# VCOBoard.net
KiCad netlist of a schematic drawn in EAGLE
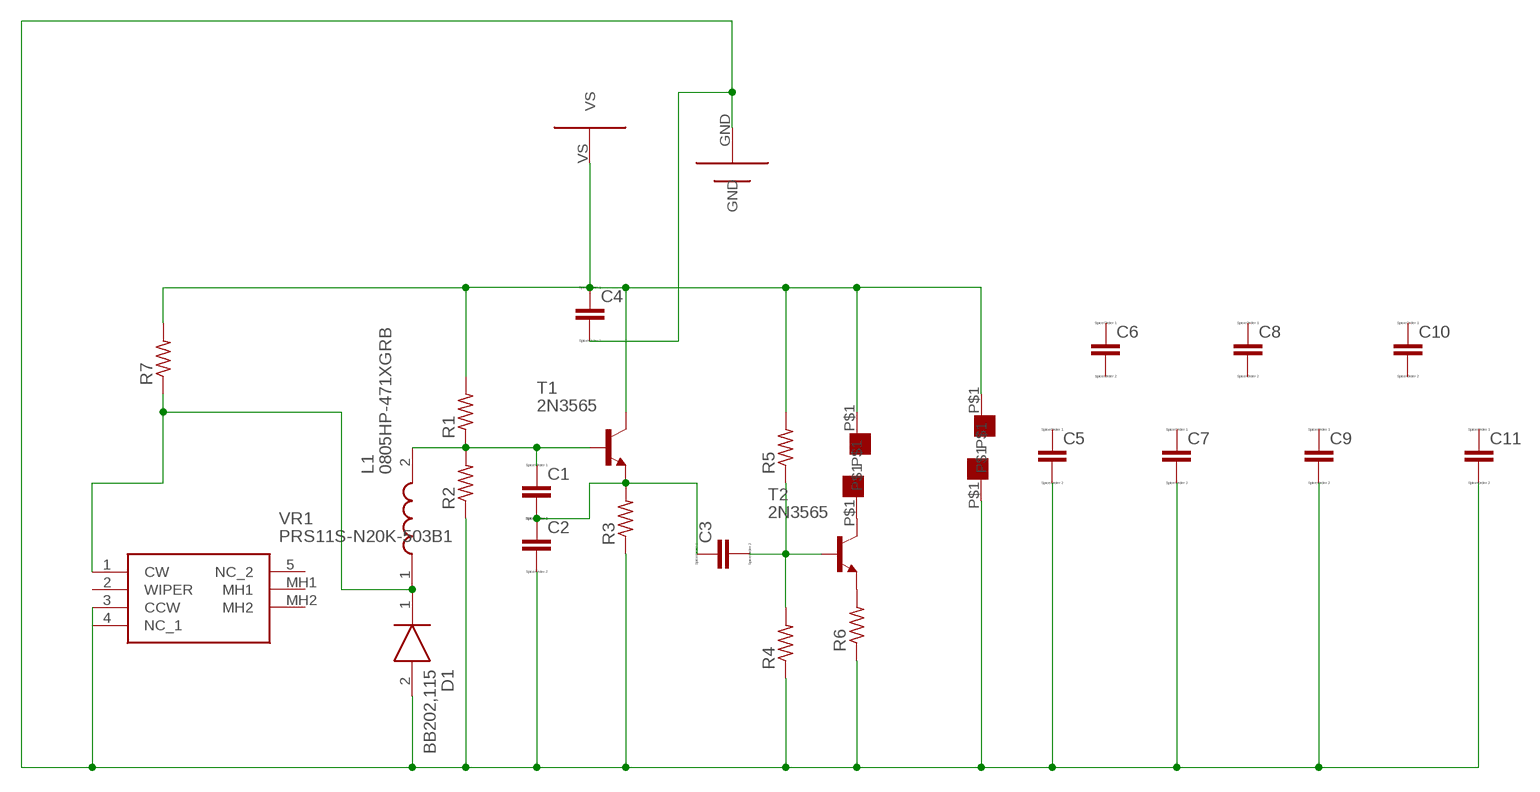
[diagram p0: schematic, sheet 1]

(export (version "E")
  (design (tool "Eeschema 10.0.6"))
  (components
    (comp (ref "C1") (value "C") (footprint "eagle-import:C0805") (libsource (lib "eagle-import") (part "C")))
    (comp (ref "C2") (value "C") (footprint "eagle-import:C0805") (libsource (lib "eagle-import") (part "C")))
    (comp (ref "C3") (value "C") (footprint "eagle-import:C0805") (libsource (lib "eagle-import") (part "C")))
    (comp (ref "C4") (value "C") (footprint "eagle-import:C0805") (libsource (lib "eagle-import") (part "C")))
    (comp (ref "C5") (value "C") (footprint "eagle-import:C0805") (libsource (lib "eagle-import") (part "C")))
    (comp (ref "C6") (value "C") (footprint "eagle-import:C0805") (libsource (lib "eagle-import") (part "C")))
    (comp (ref "C7") (value "C") (footprint "eagle-import:C0805") (libsource (lib "eagle-import") (part "C")))
    (comp (ref "C8") (value "C") (footprint "eagle-import:C0805") (libsource (lib "eagle-import") (part "C")))
    (comp (ref "C9") (value "C") (footprint "eagle-import:C0805") (libsource (lib "eagle-import") (part "C")))
    (comp (ref "C10")
      (value "C")
      (footprint "eagle-import:C0805")
      (libsource (lib "eagle-import") (part "C"))
    )
    (comp (ref "C11")
      (value "C")
      (footprint "eagle-import:C0805")
      (libsource (lib "eagle-import") (part "C"))
    )
    (comp (ref "D1")
      (value "BB202,115")
      (footprint "eagle-import:SODFL1608X65N")
      (fields (field (name "MOUSER_PART_NUMBER") "771-BB202-T/R"))
      (libsource (lib "eagle-import") (part "BB202,115"))
    )
    (comp (ref "L1")
      (value "0805HP-471XGRB")
      (footprint "eagle-import:INDPM2217X155N")
      (fields (field (name "MOUSER_PART_NUMBER") "994-0805HP-471XGRB"))
      (libsource (lib "eagle-import") (part "0805HP-471XGRB"))
    )
    (comp (ref "R1")
      (value "R-US_R0805")
      (footprint "eagle-import:R0805")
      (libsource (lib "eagle-import") (part "R-US_R0805"))
    )
    (comp (ref "R2")
      (value "R-US_R0805")
      (footprint "eagle-import:R0805")
      (libsource (lib "eagle-import") (part "R-US_R0805"))
    )
    (comp (ref "R3")
      (value "R-US_R0805")
      (footprint "eagle-import:R0805")
      (libsource (lib "eagle-import") (part "R-US_R0805"))
    )
    (comp (ref "R4")
      (value "R-US_R0805")
      (footprint "eagle-import:R0805")
      (libsource (lib "eagle-import") (part "R-US_R0805"))
    )
    (comp (ref "R5")
      (value "R-US_R0805")
      (footprint "eagle-import:R0805")
      (libsource (lib "eagle-import") (part "R-US_R0805"))
    )
    (comp (ref "R6")
      (value "R-US_R0805")
      (footprint "eagle-import:R0805")
      (libsource (lib "eagle-import") (part "R-US_R0805"))
    )
    (comp (ref "R7")
      (value "R-US_R0805")
      (footprint "eagle-import:R0805")
      (libsource (lib "eagle-import") (part "R-US_R0805"))
    )
    (comp (ref "T1")
      (value "2N3565")
      (footprint "eagle-import:TO92")
      (libsource (lib "eagle-import") (part "2N3565"))
    )
    (comp (ref "T2")
      (value "2N3565")
      (footprint "eagle-import:TO92")
      (libsource (lib "eagle-import") (part "2N3565"))
    )
    (comp (ref "U$1")
      (value "PAD")
      (footprint "eagle-import:PAD")
      (libsource (lib "eagle-import") (part "PAD"))
    )
    (comp (ref "U$2")
      (value "PAD")
      (footprint "eagle-import:PAD")
      (libsource (lib "eagle-import") (part "PAD"))
    )
    (comp (ref "U$3")
      (value "PAD")
      (footprint "eagle-import:PAD")
      (libsource (lib "eagle-import") (part "PAD"))
    )
    (comp (ref "U$4")
      (value "PAD")
      (footprint "eagle-import:PAD")
      (libsource (lib "eagle-import") (part "PAD"))
    )
    (comp (ref "U$5")
      (value "ALLIGATORCLIPS")
      (footprint "eagle-import:ALLIGATORCONNECTOR")
      (libsource (lib "eagle-import") (part "ALLIGATORCLIPS"))
    )
    (comp (ref "VR1")
      (value "PRS11S-N20K-503B1")
      (footprint "eagle-import:PRS11SN20K503B1")
      (fields (field (name "MOUSER_PART_NUMBER") "652-PRS11SN20K503B1"))
      (libsource (lib "eagle-import") (part "PRS11S-N20K-503B1"))
    )
  )
  (nets
    (net (code "1") (name "Net-(D1-A)") (class "Default")
      (node (ref "C11") (pin "2") (pinfunction "2_2") (pintype "passive"))
      (node (ref "C2") (pin "2") (pinfunction "2_2") (pintype "passive"))
      (node (ref "C4") (pin "2") (pinfunction "2_2") (pintype "passive"))
      (node (ref "C5") (pin "2") (pinfunction "2_2") (pintype "passive"))
      (node (ref "C7") (pin "2") (pinfunction "2_2") (pintype "passive"))
      (node (ref "C9") (pin "2") (pinfunction "2_2") (pintype "passive"))
      (node (ref "D1") (pin "2") (pinfunction "A_2") (pintype "bidirectional"))
      (node (ref "R2") (pin "1") (pinfunction "1_1") (pintype "passive"))
      (node (ref "R3") (pin "1") (pinfunction "1_1") (pintype "passive"))
      (node (ref "R4") (pin "1") (pinfunction "1_1") (pintype "passive"))
      (node (ref "R6") (pin "1") (pinfunction "1_1") (pintype "passive"))
      (node (ref "U$4") (pin "P$1") (pinfunction "P$1_P$1") (pintype "bidirectional"))
      (node (ref "U$5") (pin "GND") (pinfunction "GND_GND") (pintype "bidirectional"))
      (node (ref "VR1") (pin "3") (pinfunction "CCW_3") (pintype "bidirectional"))
    )
    (net (code "2") (name "Net-(D1-K)") (class "Default")
      (node (ref "D1") (pin "1") (pinfunction "K_1") (pintype "bidirectional"))
      (node (ref "L1") (pin "1") (pinfunction "1_1") (pintype "bidirectional"))
      (node (ref "R7") (pin "1") (pinfunction "1_1") (pintype "passive"))
      (node (ref "VR1") (pin "1") (pinfunction "CW_1") (pintype "bidirectional"))
    )
    (net (code "3") (name "Net-(T1-B)") (class "Default")
      (node (ref "C1") (pin "1") (pinfunction "1_1") (pintype "passive"))
      (node (ref "L1") (pin "2") (pinfunction "2_2") (pintype "bidirectional"))
      (node (ref "R1") (pin "1") (pinfunction "1_1") (pintype "passive"))
      (node (ref "R2") (pin "2") (pinfunction "2_2") (pintype "passive"))
      (node (ref "T1") (pin "2") (pinfunction "B_2") (pintype "passive"))
    )
    (net (code "4") (name "Net-(T1-C)") (class "Default")
      (node (ref "C4") (pin "1") (pinfunction "1_1") (pintype "passive"))
      (node (ref "R1") (pin "2") (pinfunction "2_2") (pintype "passive"))
      (node (ref "R5") (pin "2") (pinfunction "2_2") (pintype "passive"))
      (node (ref "R7") (pin "2") (pinfunction "2_2") (pintype "passive"))
      (node (ref "T1") (pin "1") (pinfunction "C_1") (pintype "passive"))
      (node (ref "U$2") (pin "P$1") (pinfunction "P$1_P$1") (pintype "bidirectional"))
      (node (ref "U$3") (pin "P$1") (pinfunction "P$1_P$1") (pintype "bidirectional"))
      (node (ref "U$5") (pin "VS") (pinfunction "VS_VS") (pintype "bidirectional"))
    )
    (net (code "5") (name "Net-(T1-E)") (class "Default")
      (node (ref "C1") (pin "2") (pinfunction "2_2") (pintype "passive"))
      (node (ref "C2") (pin "1") (pinfunction "1_1") (pintype "passive"))
      (node (ref "C3") (pin "1") (pinfunction "1_1") (pintype "passive"))
      (node (ref "R3") (pin "2") (pinfunction "2_2") (pintype "passive"))
      (node (ref "T1") (pin "3") (pinfunction "E_3") (pintype "passive"))
    )
    (net (code "6") (name "Net-(T2-B)") (class "Default")
      (node (ref "C3") (pin "2") (pinfunction "2_2") (pintype "passive"))
      (node (ref "R4") (pin "2") (pinfunction "2_2") (pintype "passive"))
      (node (ref "R5") (pin "1") (pinfunction "1_1") (pintype "passive"))
      (node (ref "T2") (pin "2") (pinfunction "B_2") (pintype "passive"))
    )
    (net (code "7") (name "Net-(T2-C)") (class "Default")
      (node (ref "T2") (pin "1") (pinfunction "C_1") (pintype "passive"))
      (node (ref "U$1") (pin "P$1") (pinfunction "P$1_P$1") (pintype "bidirectional"))
    )
    (net (code "8") (name "Net-(T2-E)") (class "Default")
      (node (ref "R6") (pin "2") (pinfunction "2_2") (pintype "passive"))
      (node (ref "T2") (pin "3") (pinfunction "E_3") (pintype "passive"))
    )
    (net (code "9") (name "unconnected-(C5-Pad1)") (class "Default")
      (node (ref "C5") (pin "1") (pinfunction "1_1") (pintype "passive"))
    )
    (net (code "10") (name "unconnected-(C6-Pad1)") (class "Default")
      (node (ref "C6") (pin "1") (pinfunction "1_1") (pintype "passive"))
    )
    (net (code "11") (name "unconnected-(C6-Pad2)") (class "Default")
      (node (ref "C6") (pin "2") (pinfunction "2_2") (pintype "passive"))
    )
    (net (code "12") (name "unconnected-(C7-Pad1)") (class "Default")
      (node (ref "C7") (pin "1") (pinfunction "1_1") (pintype "passive"))
    )
    (net (code "13") (name "unconnected-(C8-Pad1)") (class "Default")
      (node (ref "C8") (pin "1") (pinfunction "1_1") (pintype "passive"))
    )
    (net (code "14") (name "unconnected-(C8-Pad2)") (class "Default")
      (node (ref "C8") (pin "2") (pinfunction "2_2") (pintype "passive"))
    )
    (net (code "15") (name "unconnected-(C9-Pad1)") (class "Default")
      (node (ref "C9") (pin "1") (pinfunction "1_1") (pintype "passive"))
    )
    (net (code "16") (name "unconnected-(C10-Pad1)") (class "Default")
      (node (ref "C10") (pin "1") (pinfunction "1_1") (pintype "passive"))
    )
    (net (code "17") (name "unconnected-(C10-Pad2)") (class "Default")
      (node (ref "C10") (pin "2") (pinfunction "2_2") (pintype "passive"))
    )
    (net (code "18") (name "unconnected-(C11-Pad1)") (class "Default")
      (node (ref "C11") (pin "1") (pinfunction "1_1") (pintype "passive"))
    )
    (net (code "19") (name "unconnected-(VR1-NC_1-Pad4)") (class "Default")
      (node (ref "VR1") (pin "4") (pinfunction "NC_1_4") (pintype "bidirectional"))
    )
    (net (code "20") (name "unconnected-(VR1-NC_2-Pad5)") (class "Default")
      (node (ref "VR1") (pin "5") (pinfunction "NC_2_5") (pintype "bidirectional"))
    )
    (net (code "21") (name "unconnected-(VR1-PadMH1)") (class "Default")
      (node (ref "VR1") (pin "MH1") (pinfunction "MH1_MH1") (pintype "bidirectional"))
    )
    (net (code "22") (name "unconnected-(VR1-PadMH2)") (class "Default")
      (node (ref "VR1") (pin "MH2") (pinfunction "MH2_MH2") (pintype "bidirectional"))
    )
    (net (code "23") (name "unconnected-(VR1-WIPER-Pad2)") (class "Default")
      (node (ref "VR1") (pin "2") (pinfunction "WIPER_2") (pintype "bidirectional"))
    )
  )
)
